# AMG8854_v2.net
KiCad netlist of a schematic drawn in EAGLE
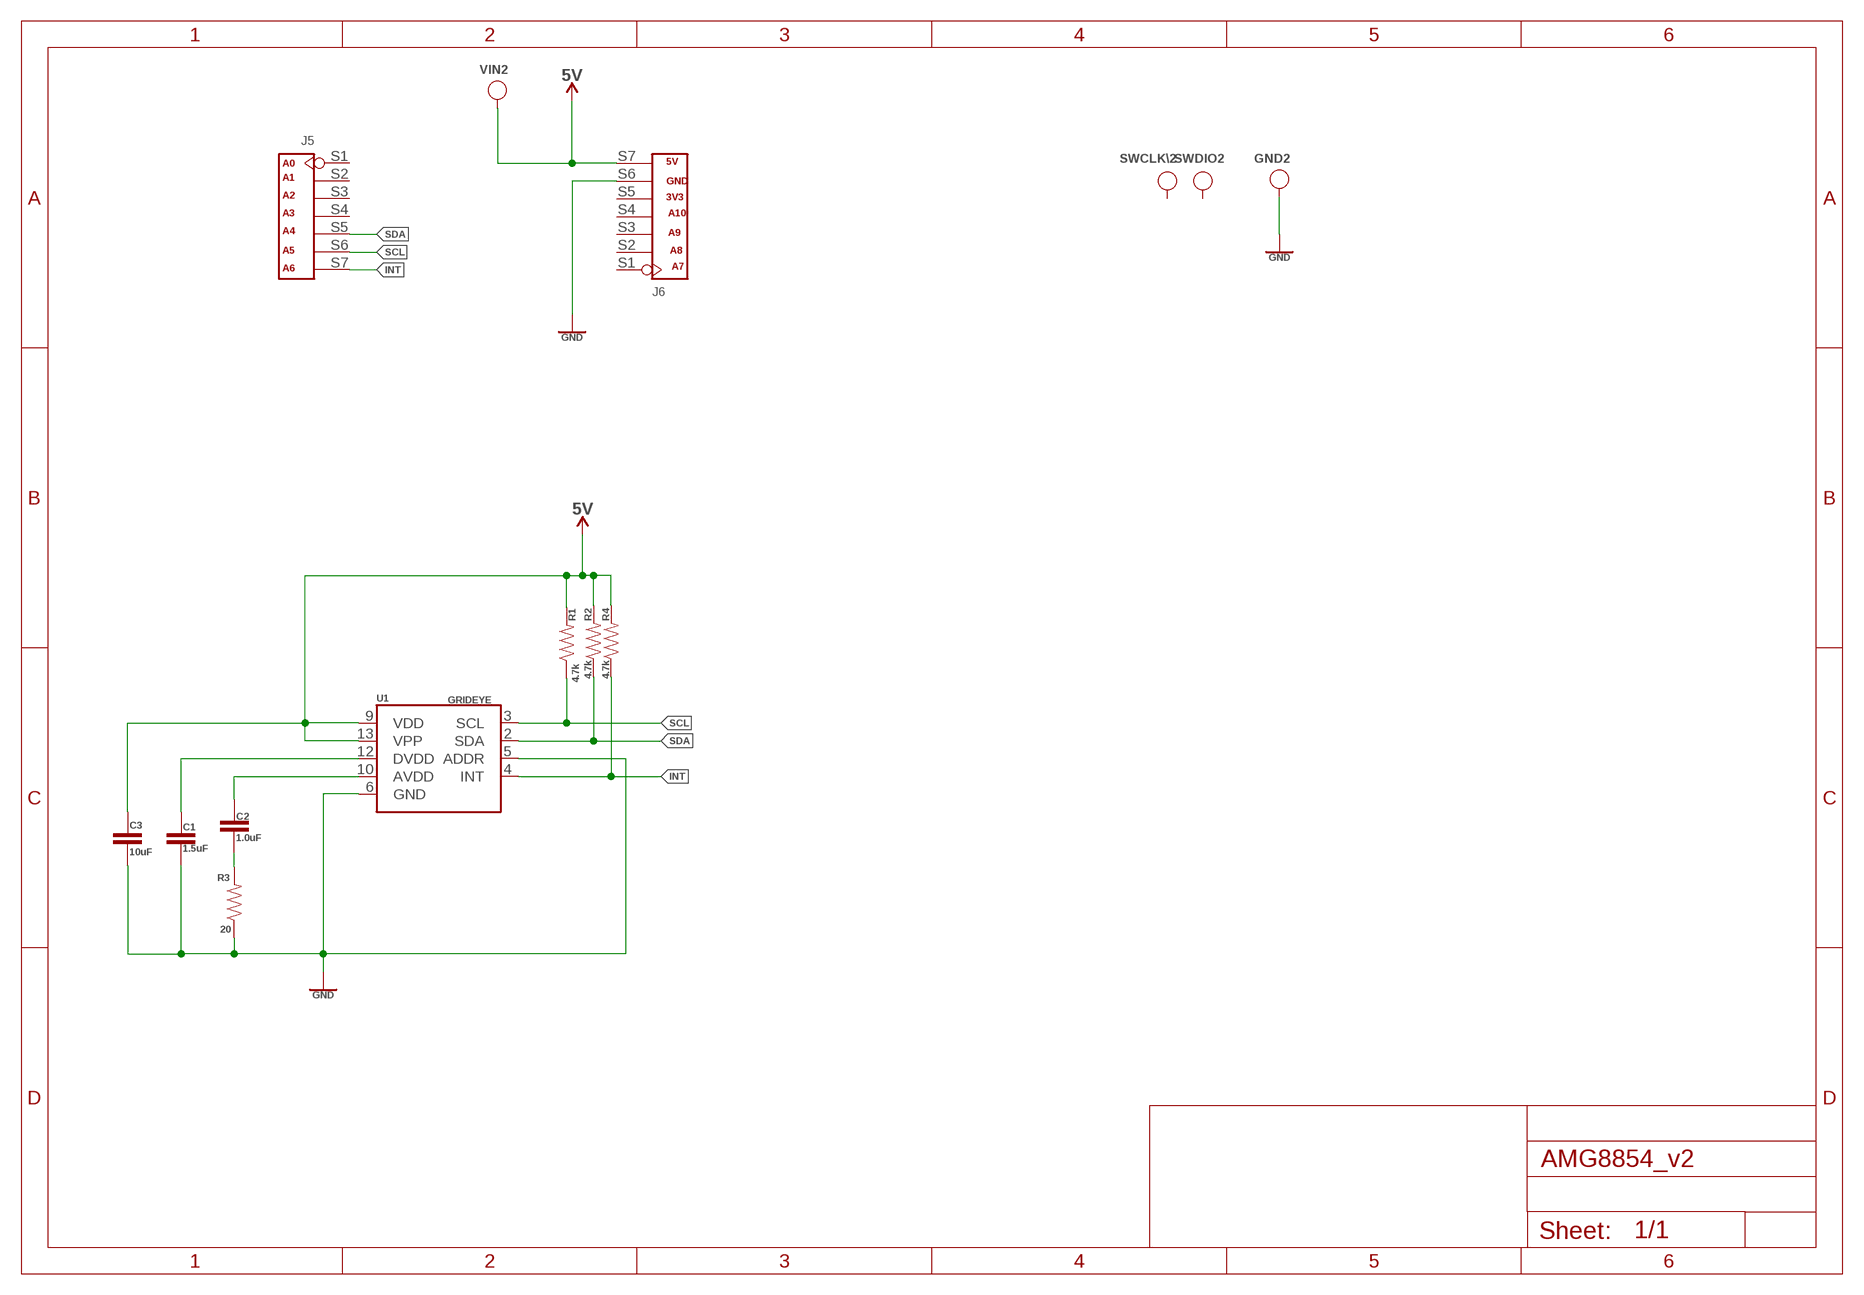
[diagram p0: schematic, sheet 1]

(export (version "E")
  (design (tool "Eeschema 10.0.6"))
  (components
    (comp (ref "C1")
      (value "1.5uF")
      (footprint "eagle-import:0603")
      (libsource (lib "eagle-import") (part "1.0UF-0603-16V-10%"))
    )
    (comp (ref "C2")
      (value "1.0uF")
      (footprint "eagle-import:0603")
      (libsource (lib "eagle-import") (part "1.0UF-0603-16V-10%"))
    )
    (comp (ref "C3")
      (value "10uF")
      (footprint "eagle-import:0603")
      (libsource (lib "eagle-import") (part "10UF-0603-6.3V-20%"))
    )
    (comp (ref "GND2")
      (value "TEST-POINT'4080'")
      (footprint "eagle-import:TP-80X40MIL")
      (libsource (lib "eagle-import") (part "TEST-POINT'4080'"))
    )
    (comp (ref "J5")
      (value "DNP")
      (footprint "eagle-import:CONNECTOR-V2")
      (libsource (lib "eagle-import") (part "CONNECTOR-NEW_HEADER-7P-HALF-HOLE"))
    )
    (comp (ref "J6")
      (value "DNP")
      (footprint "eagle-import:CONNECTOR-V2")
      (libsource (lib "eagle-import") (part "CONNECTOR-NEW_HEADER-7P-HALF-HOLE"))
    )
    (comp (ref "R1")
      (value "4.7k")
      (footprint "eagle-import:0603")
      (libsource (lib "eagle-import") (part "4.7KOHM-0603-1/10W-1%"))
    )
    (comp (ref "R2")
      (value "4.7k")
      (footprint "eagle-import:0603")
      (libsource (lib "eagle-import") (part "4.7KOHM-0603-1/10W-1%"))
    )
    (comp (ref "R3")
      (value "20")
      (footprint "eagle-import:0603")
      (libsource (lib "eagle-import") (part "20OHM-0603-1/10W-1%"))
    )
    (comp (ref "R4")
      (value "4.7k")
      (footprint "eagle-import:0603")
      (libsource (lib "eagle-import") (part "4.7KOHM-0603-1/10W-1%"))
    )
    (comp (ref "SWCLK\\2")
      (value "TEST-POINT'4545'")
      (footprint "eagle-import:TP-D45MIL")
      (fields (field (name "PARTNO") "DNP"))
      (libsource (lib "eagle-import") (part "TEST-POINT'4545'"))
    )
    (comp (ref "SWDIO2")
      (value "TEST-POINT'4545'")
      (footprint "eagle-import:TP-D45MIL")
      (fields (field (name "PARTNO") "DNP"))
      (libsource (lib "eagle-import") (part "TEST-POINT'4545'"))
    )
    (comp (ref "U1")
      (value "GRIDEYE")
      (footprint "eagle-import:GRIDEYE-AMG88")
      (libsource (lib "eagle-import") (part "GRIDEYE"))
    )
    (comp (ref "VIN2")
      (value "TEST-POINT'4080'")
      (footprint "eagle-import:TP-80X40MIL")
      (libsource (lib "eagle-import") (part "TEST-POINT'4080'"))
    )
  )
  (nets
    (net (code "1") (name "5V") (class "Default")
      (node (ref "C3") (pin "1") (pinfunction "1_1") (pintype "passive"))
      (node (ref "J6") (pin "S7") (pinfunction "7_S7") (pintype "bidirectional"))
      (node (ref "R1") (pin "2") (pinfunction "2_2") (pintype "passive"))
      (node (ref "R2") (pin "2") (pinfunction "2_2") (pintype "passive"))
      (node (ref "R4") (pin "2") (pinfunction "2_2") (pintype "passive"))
      (node (ref "U1") (pin "13") (pinfunction "VPP_13") (pintype "bidirectional"))
      (node (ref "U1") (pin "9") (pinfunction "VDD_9") (pintype "bidirectional"))
      (node (ref "VIN2") (pin "1") (pinfunction "T_1") (pintype "bidirectional"))
    )
    (net (code "2") (name "GND") (class "Default")
      (node (ref "C1") (pin "2") (pinfunction "2_2") (pintype "passive"))
      (node (ref "C3") (pin "2") (pinfunction "2_2") (pintype "passive"))
      (node (ref "GND2") (pin "1") (pinfunction "T_1") (pintype "bidirectional"))
      (node (ref "J6") (pin "S6") (pinfunction "6_S6") (pintype "bidirectional"))
      (node (ref "R3") (pin "1") (pinfunction "1_1") (pintype "passive"))
      (node (ref "U1") (pin "5") (pinfunction "ADDR_5") (pintype "bidirectional"))
      (node (ref "U1") (pin "6") (pinfunction "GND_6") (pintype "bidirectional"))
    )
    (net (code "3") (name "INT") (class "Default")
      (node (ref "J5") (pin "S7") (pinfunction "7_S7") (pintype "bidirectional"))
      (node (ref "R4") (pin "1") (pinfunction "1_1") (pintype "passive"))
      (node (ref "U1") (pin "4") (pinfunction "INT_4") (pintype "bidirectional"))
    )
    (net (code "4") (name "Net-(C2-Pad2)") (class "Default")
      (node (ref "C2") (pin "2") (pinfunction "2_2") (pintype "passive"))
      (node (ref "R3") (pin "2") (pinfunction "2_2") (pintype "passive"))
    )
    (net (code "5") (name "Net-(U1-AVDD)") (class "Default")
      (node (ref "C2") (pin "1") (pinfunction "1_1") (pintype "passive"))
      (node (ref "U1") (pin "10") (pinfunction "AVDD_10") (pintype "bidirectional"))
    )
    (net (code "6") (name "Net-(U1-DVDD)") (class "Default")
      (node (ref "C1") (pin "1") (pinfunction "1_1") (pintype "passive"))
      (node (ref "U1") (pin "12") (pinfunction "DVDD_12") (pintype "bidirectional"))
    )
    (net (code "7") (name "SCL") (class "Default")
      (node (ref "J5") (pin "S6") (pinfunction "6_S6") (pintype "bidirectional"))
      (node (ref "R1") (pin "1") (pinfunction "1_1") (pintype "passive"))
      (node (ref "U1") (pin "3") (pinfunction "SCL_3") (pintype "bidirectional"))
    )
    (net (code "8") (name "SDA") (class "Default")
      (node (ref "J5") (pin "S5") (pinfunction "5_S5") (pintype "bidirectional"))
      (node (ref "R2") (pin "1") (pinfunction "1_1") (pintype "passive"))
      (node (ref "U1") (pin "2") (pinfunction "SDA_2") (pintype "bidirectional"))
    )
    (net (code "9") (name "unconnected-(J5-1-PadS1)") (class "Default")
      (node (ref "J5") (pin "S1") (pinfunction "1_S1") (pintype "bidirectional"))
    )
    (net (code "10") (name "unconnected-(J5-2-PadS2)") (class "Default")
      (node (ref "J5") (pin "S2") (pinfunction "2_S2") (pintype "bidirectional"))
    )
    (net (code "11") (name "unconnected-(J5-3-PadS3)") (class "Default")
      (node (ref "J5") (pin "S3") (pinfunction "3_S3") (pintype "bidirectional"))
    )
    (net (code "12") (name "unconnected-(J5-4-PadS4)") (class "Default")
      (node (ref "J5") (pin "S4") (pinfunction "4_S4") (pintype "bidirectional"))
    )
    (net (code "13") (name "unconnected-(J6-1-PadS1)") (class "Default")
      (node (ref "J6") (pin "S1") (pinfunction "1_S1") (pintype "bidirectional"))
    )
    (net (code "14") (name "unconnected-(J6-2-PadS2)") (class "Default")
      (node (ref "J6") (pin "S2") (pinfunction "2_S2") (pintype "bidirectional"))
    )
    (net (code "15") (name "unconnected-(J6-3-PadS3)") (class "Default")
      (node (ref "J6") (pin "S3") (pinfunction "3_S3") (pintype "bidirectional"))
    )
    (net (code "16") (name "unconnected-(J6-4-PadS4)") (class "Default")
      (node (ref "J6") (pin "S4") (pinfunction "4_S4") (pintype "bidirectional"))
    )
    (net (code "17") (name "unconnected-(J6-5-PadS5)") (class "Default")
      (node (ref "J6") (pin "S5") (pinfunction "5_S5") (pintype "bidirectional"))
    )
    (net (code "18") (name "unconnected-(SWCLK\\2-PadT)") (class "Default")
      (node (ref "SWCLK\\2") (pin "T") (pinfunction "T_T") (pintype "bidirectional"))
    )
    (net (code "19") (name "unconnected-(SWDIO2-PadT)") (class "Default")
      (node (ref "SWDIO2") (pin "T") (pinfunction "T_T") (pintype "bidirectional"))
    )
  )
)
